# WaterMonitorV2_1.net
KiCad netlist of a schematic drawn in EAGLE
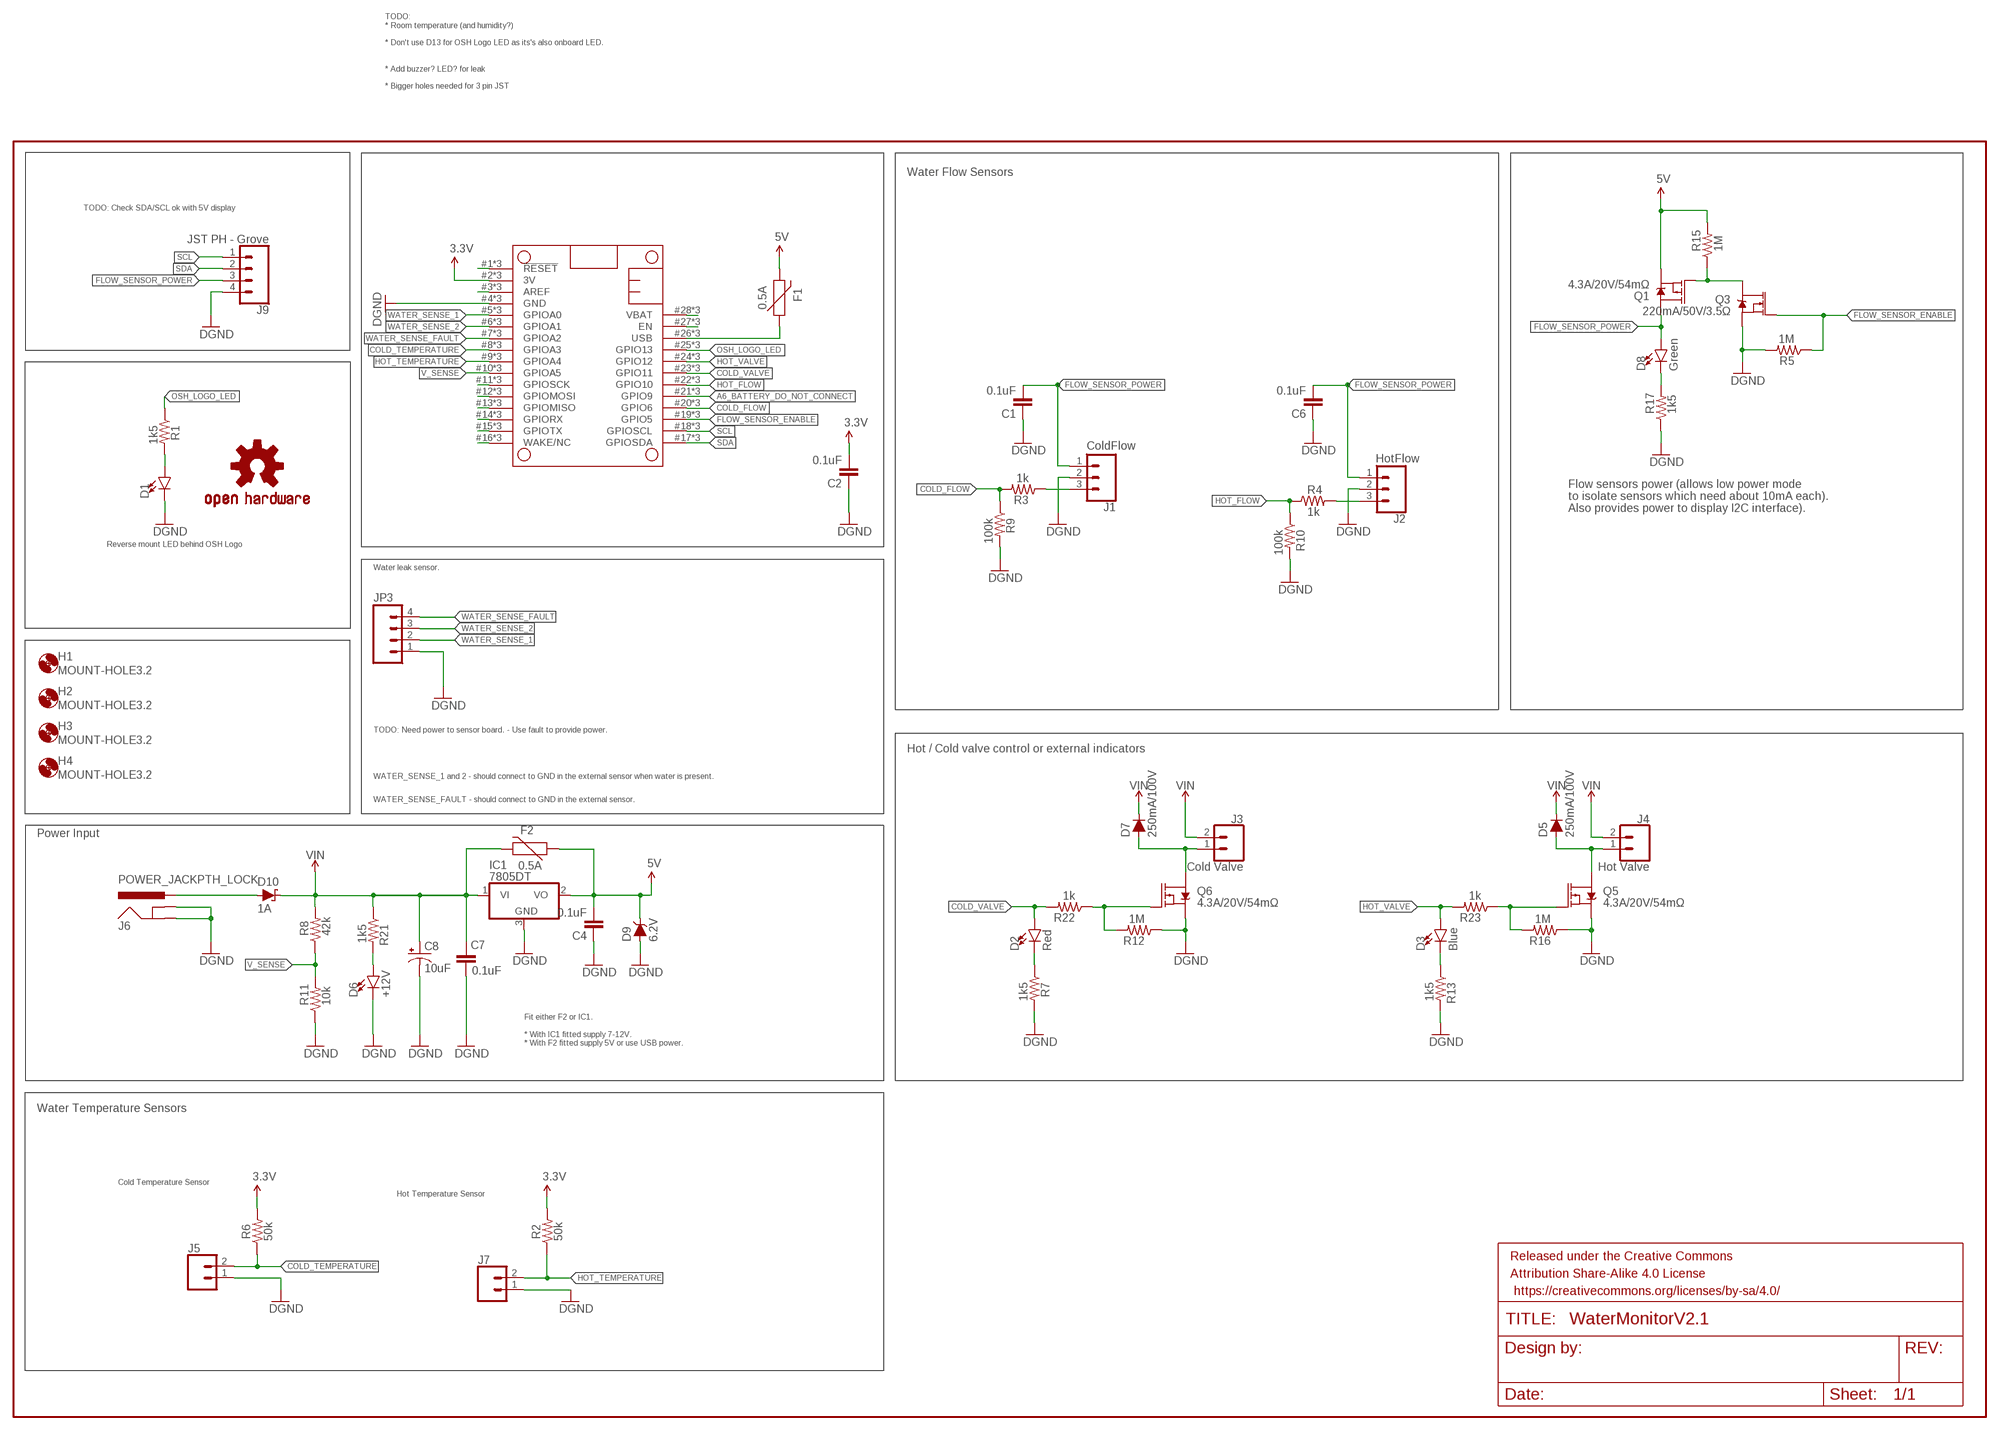
[diagram p0: schematic, sheet 1]

(export (version "E")
  (design (tool "Eeschema 10.0.6"))
  (components
    (comp (ref "C1")
      (value "0.1uF")
      (footprint "eagle-import:0805")
      (libsource (lib "eagle-import") (part "CAP0805"))
    )
    (comp (ref "C2")
      (value "0.1uF")
      (footprint "eagle-import:0805")
      (libsource (lib "eagle-import") (part "CAP0805"))
    )
    (comp (ref "C4")
      (value "0.1uF")
      (footprint "eagle-import:0805")
      (libsource (lib "eagle-import") (part "CAP0805"))
    )
    (comp (ref "C6")
      (value "0.1uF")
      (footprint "eagle-import:0805")
      (libsource (lib "eagle-import") (part "CAP0805"))
    )
    (comp (ref "C7")
      (value "0.1uF")
      (footprint "eagle-import:0805")
      (libsource (lib "eagle-import") (part "CAP0805"))
    )
    (comp (ref "C8")
      (value "10uF")
      (footprint "eagle-import:EIA3216")
      (libsource (lib "eagle-import") (part "10UF-POLAR-EIA3216-16V-10%(TANT)"))
    )
    (comp (ref "D1")
      (value "LED1206-BOTTOM")
      (footprint "eagle-import:LED-1206-BOTTOM")
      (libsource (lib "eagle-import") (part "LED1206-BOTTOM"))
    )
    (comp (ref "D2")
      (value "Red")
      (footprint "eagle-import:LED-1206")
      (libsource (lib "eagle-import") (part "LED-BLUE1206"))
    )
    (comp (ref "D3")
      (value "Blue")
      (footprint "eagle-import:LED-1206")
      (libsource (lib "eagle-import") (part "LED-BLUE1206"))
    )
    (comp (ref "D5")
      (value "250mA/100V")
      (footprint "eagle-import:SOD-323")
      (libsource (lib "eagle-import") (part "DIODE-BAS16J"))
    )
    (comp (ref "D6")
      (value "+12V")
      (footprint "eagle-import:LED-1206")
      (libsource (lib "eagle-import") (part "LED-BLUE1206"))
    )
    (comp (ref "D7")
      (value "250mA/100V")
      (footprint "eagle-import:SOD-323")
      (libsource (lib "eagle-import") (part "DIODE-BAS16J"))
    )
    (comp (ref "D8")
      (value "Green")
      (footprint "eagle-import:LED-1206")
      (libsource (lib "eagle-import") (part "LED-BLUE1206"))
    )
    (comp (ref "D9")
      (value "6.2V")
      (footprint "eagle-import:SOD-323")
      (fields (field (name "MFG") "BZT52C6V2"))
      (libsource (lib "eagle-import") (part "DIODE-ZENER-BZT52C3V6S"))
    )
    (comp (ref "D10")
      (value "1A")
      (footprint "eagle-import:SMA-DIODE")
      (libsource (lib "eagle-import") (part "DIODE-SCHOTTKY-B340A"))
    )
    (comp (ref "F1")
      (value "0.5A")
      (footprint "eagle-import:1206")
      (libsource (lib "eagle-import") (part "PPTC_HALF-AMP"))
    )
    (comp (ref "F2")
      (value "0.5A")
      (footprint "eagle-import:1206")
      (libsource (lib "eagle-import") (part "PPTC_HALF-AMP"))
    )
    (comp (ref "FRAME2")
      (value "FRAME-LEDGER")
      (footprint "eagle-import:CREATIVE_COMMONS")
      (libsource (lib "eagle-import") (part "FRAME-LEDGER"))
    )
    (comp (ref "H1")
      (value "MOUNT-HOLE3.2")
      (footprint "eagle-import:3,2")
      (libsource (lib "eagle-import") (part "MOUNT-HOLE3.2"))
    )
    (comp (ref "H2")
      (value "MOUNT-HOLE3.2")
      (footprint "eagle-import:3,2")
      (libsource (lib "eagle-import") (part "MOUNT-HOLE3.2"))
    )
    (comp (ref "H3")
      (value "MOUNT-HOLE3.2")
      (footprint "eagle-import:3,2")
      (libsource (lib "eagle-import") (part "MOUNT-HOLE3.2"))
    )
    (comp (ref "H4")
      (value "MOUNT-HOLE3.2")
      (footprint "eagle-import:3,2")
      (libsource (lib "eagle-import") (part "MOUNT-HOLE3.2"))
    )
    (comp (ref "IC1")
      (value "7805DT")
      (footprint "eagle-import:TO252")
      (libsource (lib "eagle-import") (part "78DT05"))
    )
    (comp (ref "J1")
      (value "ColdFlow")
      (footprint "eagle-import:JST-HX-3-PTH-VERT")
      (libsource (lib "eagle-import") (part "CONN_03JST-HX-PTH-VERT"))
    )
    (comp (ref "J2")
      (value "HotFlow")
      (footprint "eagle-import:JST-HX-3-PTH-VERT")
      (libsource (lib "eagle-import") (part "CONN_03JST-HX-PTH-VERT"))
    )
    (comp (ref "J3")
      (value "Cold Valve")
      (footprint "eagle-import:SCREWTERMINAL-5MM-2")
      (libsource (lib "eagle-import") (part "CONN_025MM"))
    )
    (comp (ref "J4")
      (value "Hot Valve")
      (footprint "eagle-import:SCREWTERMINAL-5MM-2")
      (libsource (lib "eagle-import") (part "CONN_025MM"))
    )
    (comp (ref "J5")
      (value "CONN_02POLAR")
      (footprint "eagle-import:MOLEX-1X2")
      (libsource (lib "eagle-import") (part "CONN_02POLAR"))
    )
    (comp (ref "J6")
      (value "POWER_JACKPTH_LOCK")
      (footprint "eagle-import:POWER_JACK_PTH_LOCK")
      (libsource (lib "eagle-import") (part "POWER_JACKPTH_LOCK"))
    )
    (comp (ref "J7")
      (value "CONN_02POLAR")
      (footprint "eagle-import:MOLEX-1X2")
      (libsource (lib "eagle-import") (part "CONN_02POLAR"))
    )
    (comp (ref "J9")
      (value "JST PH - Grove")
      (footprint "eagle-import:JST-4-PTH-VERT")
      (libsource (lib "eagle-import") (part "CONN_04JST-PTH-VERT"))
    )
    (comp (ref "JP3")
      (value "M04POLAR")
      (footprint "eagle-import:MOLEX-1X4@1")
      (libsource (lib "eagle-import") (part "M04POLAR"))
    )
    (comp (ref "LOGO1")
      (value "OSHW-LOGOM")
      (footprint "eagle-import:OSHW-LOGO-M")
      (libsource (lib "eagle-import") (part "OSHW-LOGOM"))
    )
    (comp (ref "MS1")
      (value "FEATHERWINGFEATHEWING_BREAKOUT")
      (footprint "eagle-import:FEATHERWING_BREAKOUT")
      (libsource (lib "eagle-import") (part "FEATHERWINGFEATHEWING_BREAKOUT"))
    )
    (comp (ref "Q1")
      (value "4.3A/20V/54mΩ")
      (footprint "eagle-import:SOT23-3")
      (libsource (lib "eagle-import") (part "MOSFET_PCH-IRLML2244"))
    )
    (comp (ref "Q3")
      (value "220mA/50V/3.5Ω")
      (footprint "eagle-import:SOT23-3")
      (libsource (lib "eagle-import") (part "MOSFET-NCH-BSS138"))
    )
    (comp (ref "Q5")
      (value "4.3A/20V/54mΩ")
      (footprint "eagle-import:SOT23-3")
      (libsource (lib "eagle-import") (part "MOSFET_PCH-IRLML2244"))
    )
    (comp (ref "Q6")
      (value "4.3A/20V/54mΩ")
      (footprint "eagle-import:SOT23-3")
      (libsource (lib "eagle-import") (part "MOSFET_PCH-IRLML2244"))
    )
    (comp (ref "R1")
      (value "1k5")
      (footprint "eagle-import:0805")
      (libsource (lib "eagle-import") (part "RESISTOR0805"))
    )
    (comp (ref "R2")
      (value "50k")
      (footprint "eagle-import:0805")
      (libsource (lib "eagle-import") (part "RESISTOR0805"))
    )
    (comp (ref "R3")
      (value "1k")
      (footprint "eagle-import:0805")
      (libsource (lib "eagle-import") (part "RESISTOR0805"))
    )
    (comp (ref "R4")
      (value "1k")
      (footprint "eagle-import:0805")
      (libsource (lib "eagle-import") (part "RESISTOR0805"))
    )
    (comp (ref "R5")
      (value "1M")
      (footprint "eagle-import:0805")
      (libsource (lib "eagle-import") (part "RESISTOR0805"))
    )
    (comp (ref "R6")
      (value "50k")
      (footprint "eagle-import:0805")
      (libsource (lib "eagle-import") (part "RESISTOR0805"))
    )
    (comp (ref "R7")
      (value "1k5")
      (footprint "eagle-import:0805")
      (libsource (lib "eagle-import") (part "RESISTOR0805"))
    )
    (comp (ref "R8")
      (value "42k")
      (footprint "eagle-import:0805")
      (libsource (lib "eagle-import") (part "RESISTOR0805"))
    )
    (comp (ref "R9")
      (value "100k")
      (footprint "eagle-import:0805")
      (libsource (lib "eagle-import") (part "RESISTOR0805"))
    )
    (comp (ref "R10")
      (value "100k")
      (footprint "eagle-import:0805")
      (libsource (lib "eagle-import") (part "RESISTOR0805"))
    )
    (comp (ref "R11")
      (value "10k")
      (footprint "eagle-import:0805")
      (libsource (lib "eagle-import") (part "RESISTOR0805"))
    )
    (comp (ref "R12")
      (value "1M")
      (footprint "eagle-import:0805")
      (libsource (lib "eagle-import") (part "RESISTOR0805"))
    )
    (comp (ref "R13")
      (value "1k5")
      (footprint "eagle-import:0805")
      (libsource (lib "eagle-import") (part "RESISTOR0805"))
    )
    (comp (ref "R15")
      (value "1M")
      (footprint "eagle-import:0805")
      (libsource (lib "eagle-import") (part "RESISTOR0805"))
    )
    (comp (ref "R16")
      (value "1M")
      (footprint "eagle-import:0805")
      (libsource (lib "eagle-import") (part "RESISTOR0805"))
    )
    (comp (ref "R17")
      (value "1k5")
      (footprint "eagle-import:0805")
      (libsource (lib "eagle-import") (part "RESISTOR0805"))
    )
    (comp (ref "R21")
      (value "1k5")
      (footprint "eagle-import:0805")
      (libsource (lib "eagle-import") (part "RESISTOR0805"))
    )
    (comp (ref "R22")
      (value "1k")
      (footprint "eagle-import:0805")
      (libsource (lib "eagle-import") (part "RESISTOR0805"))
    )
    (comp (ref "R23")
      (value "1k")
      (footprint "eagle-import:0805")
      (libsource (lib "eagle-import") (part "RESISTOR0805"))
    )
  )
  (nets
    (net (code "1") (name "3.3V") (class "Default")
      (node (ref "C2") (pin "2") (pinfunction "2_2") (pintype "passive"))
      (node (ref "MS1") (pin "#2") (pinfunction "3V_#2") (pintype "power_in"))
      (node (ref "MS1") (pin "2") (pinfunction "3V_2") (pintype "power_in"))
      (node (ref "MS1") (pin "@2") (pinfunction "3V_@2") (pintype "power_in"))
      (node (ref "R2") (pin "2") (pinfunction "2_2") (pintype "passive"))
      (node (ref "R6") (pin "2") (pinfunction "2_2") (pintype "passive"))
    )
    (net (code "2") (name "5V") (class "Default")
      (node (ref "C4") (pin "2") (pinfunction "2_2") (pintype "passive"))
      (node (ref "D9") (pin "C") (pinfunction "C_C") (pintype "passive"))
      (node (ref "F1") (pin "2") (pinfunction "2_2") (pintype "bidirectional"))
      (node (ref "F2") (pin "1") (pinfunction "1_1") (pintype "bidirectional"))
      (node (ref "IC1") (pin "2") (pinfunction "VO_2") (pintype "passive"))
      (node (ref "Q1") (pin "2") (pinfunction "S_2") (pintype "bidirectional"))
      (node (ref "R15") (pin "2") (pinfunction "2_2") (pintype "passive"))
    )
    (net (code "3") (name "A6_BATTERY_DO_NOT_CONNECT") (class "Default")
      (node (ref "MS1") (pin "#21") (pinfunction "GPIO9_#21") (pintype "bidirectional"))
      (node (ref "MS1") (pin "21") (pinfunction "GPIO9_21") (pintype "bidirectional"))
      (node (ref "MS1") (pin "@21") (pinfunction "GPIO9_@21") (pintype "bidirectional"))
    )
    (net (code "4") (name "COLD_FLOW") (class "Default")
      (node (ref "MS1") (pin "#20") (pinfunction "GPIO6_#20") (pintype "bidirectional"))
      (node (ref "MS1") (pin "20") (pinfunction "GPIO6_20") (pintype "bidirectional"))
      (node (ref "MS1") (pin "@20") (pinfunction "GPIO6_@20") (pintype "bidirectional"))
      (node (ref "R3") (pin "2") (pinfunction "2_2") (pintype "passive"))
      (node (ref "R9") (pin "1") (pinfunction "1_1") (pintype "passive"))
    )
    (net (code "5") (name "COLD_TEMPERATURE") (class "Default")
      (node (ref "J5") (pin "2") (pinfunction "2_2") (pintype "passive"))
      (node (ref "MS1") (pin "#8") (pinfunction "GPIOA3_#8") (pintype "bidirectional"))
      (node (ref "MS1") (pin "8") (pinfunction "GPIOA3_8") (pintype "bidirectional"))
      (node (ref "MS1") (pin "@8") (pinfunction "GPIOA3_@8") (pintype "bidirectional"))
      (node (ref "R6") (pin "1") (pinfunction "1_1") (pintype "passive"))
    )
    (net (code "6") (name "COLD_VALVE") (class "Default")
      (node (ref "D2") (pin "A") (pinfunction "A_A") (pintype "passive"))
      (node (ref "MS1") (pin "#23") (pinfunction "GPIO11_#23") (pintype "bidirectional"))
      (node (ref "MS1") (pin "23") (pinfunction "GPIO11_23") (pintype "bidirectional"))
      (node (ref "MS1") (pin "@23") (pinfunction "GPIO11_@23") (pintype "bidirectional"))
      (node (ref "R22") (pin "2") (pinfunction "2_2") (pintype "passive"))
    )
    (net (code "7") (name "DGND") (class "Default")
      (node (ref "C1") (pin "1") (pinfunction "1_1") (pintype "passive"))
      (node (ref "C2") (pin "1") (pinfunction "1_1") (pintype "passive"))
      (node (ref "C4") (pin "1") (pinfunction "1_1") (pintype "passive"))
      (node (ref "C6") (pin "1") (pinfunction "1_1") (pintype "passive"))
      (node (ref "C7") (pin "1") (pinfunction "1_1") (pintype "passive"))
      (node (ref "C8") (pin "-") (pinfunction "-_-") (pintype "passive"))
      (node (ref "D1") (pin "C") (pinfunction "C_C") (pintype "passive"))
      (node (ref "D6") (pin "C") (pinfunction "C_C") (pintype "passive"))
      (node (ref "D9") (pin "A") (pinfunction "A_A") (pintype "passive"))
      (node (ref "IC1") (pin "3") (pinfunction "GND_3") (pintype "passive"))
      (node (ref "J1") (pin "2") (pinfunction "2_2") (pintype "passive"))
      (node (ref "J2") (pin "2") (pinfunction "2_2") (pintype "passive"))
      (node (ref "J5") (pin "1") (pinfunction "1_1") (pintype "passive"))
      (node (ref "J6") (pin "GND") (pinfunction "GND_GND") (pintype "bidirectional"))
      (node (ref "J6") (pin "GNDBREAK") (pinfunction "GNDBREAK_GNDBREAK") (pintype "bidirectional"))
      (node (ref "J7") (pin "1") (pinfunction "1_1") (pintype "passive"))
      (node (ref "J9") (pin "4") (pinfunction "4_4") (pintype "passive"))
      (node (ref "JP3") (pin "1") (pinfunction "1_1") (pintype "passive"))
      (node (ref "MS1") (pin "#4") (pinfunction "GND_#4") (pintype "power_in"))
      (node (ref "MS1") (pin "4") (pinfunction "GND_4") (pintype "power_in"))
      (node (ref "MS1") (pin "@4") (pinfunction "GND_@4") (pintype "power_in"))
      (node (ref "Q3") (pin "2") (pinfunction "S_2") (pintype "bidirectional"))
      (node (ref "Q5") (pin "2") (pinfunction "S_2") (pintype "bidirectional"))
      (node (ref "Q6") (pin "2") (pinfunction "S_2") (pintype "bidirectional"))
      (node (ref "R10") (pin "2") (pinfunction "2_2") (pintype "passive"))
      (node (ref "R11") (pin "1") (pinfunction "1_1") (pintype "passive"))
      (node (ref "R12") (pin "1") (pinfunction "1_1") (pintype "passive"))
      (node (ref "R13") (pin "2") (pinfunction "2_2") (pintype "passive"))
      (node (ref "R16") (pin "1") (pinfunction "1_1") (pintype "passive"))
      (node (ref "R17") (pin "1") (pinfunction "1_1") (pintype "passive"))
      (node (ref "R5") (pin "2") (pinfunction "2_2") (pintype "passive"))
      (node (ref "R7") (pin "2") (pinfunction "2_2") (pintype "passive"))
      (node (ref "R9") (pin "2") (pinfunction "2_2") (pintype "passive"))
    )
    (net (code "8") (name "FLOW_SENSOR_ENABLE") (class "Default")
      (node (ref "MS1") (pin "#19") (pinfunction "GPIO5_#19") (pintype "bidirectional"))
      (node (ref "MS1") (pin "19") (pinfunction "GPIO5_19") (pintype "bidirectional"))
      (node (ref "MS1") (pin "@19") (pinfunction "GPIO5_@19") (pintype "bidirectional"))
      (node (ref "Q3") (pin "1") (pinfunction "G_1") (pintype "bidirectional"))
      (node (ref "R5") (pin "1") (pinfunction "1_1") (pintype "passive"))
    )
    (net (code "9") (name "FLOW_SENSOR_POWER") (class "Default")
      (node (ref "C1") (pin "2") (pinfunction "2_2") (pintype "passive"))
      (node (ref "C6") (pin "2") (pinfunction "2_2") (pintype "passive"))
      (node (ref "D8") (pin "A") (pinfunction "A_A") (pintype "passive"))
      (node (ref "J1") (pin "1") (pinfunction "1_1") (pintype "passive"))
      (node (ref "J2") (pin "1") (pinfunction "1_1") (pintype "passive"))
      (node (ref "J9") (pin "3") (pinfunction "3_3") (pintype "passive"))
      (node (ref "Q1") (pin "3") (pinfunction "D_3") (pintype "bidirectional"))
    )
    (net (code "10") (name "HOT_FLOW") (class "Default")
      (node (ref "MS1") (pin "#22") (pinfunction "GPIO10_#22") (pintype "bidirectional"))
      (node (ref "MS1") (pin "22") (pinfunction "GPIO10_22") (pintype "bidirectional"))
      (node (ref "MS1") (pin "@22") (pinfunction "GPIO10_@22") (pintype "bidirectional"))
      (node (ref "R10") (pin "1") (pinfunction "1_1") (pintype "passive"))
      (node (ref "R4") (pin "1") (pinfunction "1_1") (pintype "passive"))
    )
    (net (code "11") (name "HOT_TEMPERATURE") (class "Default")
      (node (ref "J7") (pin "2") (pinfunction "2_2") (pintype "passive"))
      (node (ref "MS1") (pin "#9") (pinfunction "GPIOA4_#9") (pintype "bidirectional"))
      (node (ref "MS1") (pin "9") (pinfunction "GPIOA4_9") (pintype "bidirectional"))
      (node (ref "MS1") (pin "@9") (pinfunction "GPIOA4_@9") (pintype "bidirectional"))
      (node (ref "R2") (pin "1") (pinfunction "1_1") (pintype "passive"))
    )
    (net (code "12") (name "HOT_VALVE") (class "Default")
      (node (ref "D3") (pin "A") (pinfunction "A_A") (pintype "passive"))
      (node (ref "MS1") (pin "#24") (pinfunction "GPIO12_#24") (pintype "bidirectional"))
      (node (ref "MS1") (pin "24") (pinfunction "GPIO12_24") (pintype "bidirectional"))
      (node (ref "MS1") (pin "@24") (pinfunction "GPIO12_@24") (pintype "bidirectional"))
      (node (ref "R23") (pin "2") (pinfunction "2_2") (pintype "passive"))
    )
    (net (code "13") (name "Net-(D1-PadA)") (class "Default")
      (node (ref "D1") (pin "A") (pinfunction "A_A") (pintype "passive"))
      (node (ref "R1") (pin "2") (pinfunction "2_2") (pintype "passive"))
    )
    (net (code "14") (name "Net-(D2-PadC)") (class "Default")
      (node (ref "D2") (pin "C") (pinfunction "C_C") (pintype "passive"))
      (node (ref "R7") (pin "1") (pinfunction "1_1") (pintype "passive"))
    )
    (net (code "15") (name "Net-(D3-PadC)") (class "Default")
      (node (ref "D3") (pin "C") (pinfunction "C_C") (pintype "passive"))
      (node (ref "R13") (pin "1") (pinfunction "1_1") (pintype "passive"))
    )
    (net (code "16") (name "Net-(D6-PadA)") (class "Default")
      (node (ref "D6") (pin "A") (pinfunction "A_A") (pintype "passive"))
      (node (ref "R21") (pin "2") (pinfunction "2_2") (pintype "passive"))
    )
    (net (code "17") (name "Net-(D8-PadC)") (class "Default")
      (node (ref "D8") (pin "C") (pinfunction "C_C") (pintype "passive"))
      (node (ref "R17") (pin "2") (pinfunction "2_2") (pintype "passive"))
    )
    (net (code "18") (name "Net-(D10-PadA)") (class "Default")
      (node (ref "D10") (pin "A") (pinfunction "A_A") (pintype "passive"))
      (node (ref "J6") (pin "PWR") (pinfunction "PWR_PWR") (pintype "bidirectional"))
    )
    (net (code "19") (name "Net-(F1-Pad1)") (class "Default")
      (node (ref "F1") (pin "1") (pinfunction "1_1") (pintype "bidirectional"))
      (node (ref "MS1") (pin "#26") (pinfunction "USB_#26") (pintype "power_in"))
      (node (ref "MS1") (pin "26") (pinfunction "USB_26") (pintype "power_in"))
      (node (ref "MS1") (pin "@26") (pinfunction "USB_@26") (pintype "power_in"))
    )
    (net (code "20") (name "Net-(J1-Pad3)") (class "Default")
      (node (ref "J1") (pin "3") (pinfunction "3_3") (pintype "passive"))
      (node (ref "R3") (pin "1") (pinfunction "1_1") (pintype "passive"))
    )
    (net (code "21") (name "Net-(J2-Pad3)") (class "Default")
      (node (ref "J2") (pin "3") (pinfunction "3_3") (pintype "passive"))
      (node (ref "R4") (pin "2") (pinfunction "2_2") (pintype "passive"))
    )
    (net (code "22") (name "Net-(MS1-AREF-Pad#3)") (class "Default")
      (node (ref "MS1") (pin "#3") (pinfunction "AREF_#3") (pintype "passive"))
      (node (ref "MS1") (pin "3") (pinfunction "AREF_3") (pintype "passive"))
      (node (ref "MS1") (pin "@3") (pinfunction "AREF_@3") (pintype "passive"))
    )
    (net (code "23") (name "Net-(MS1-EN-Pad#27)") (class "Default")
      (node (ref "MS1") (pin "#27") (pinfunction "EN_#27") (pintype "passive"))
      (node (ref "MS1") (pin "27") (pinfunction "EN_27") (pintype "passive"))
      (node (ref "MS1") (pin "@27") (pinfunction "EN_@27") (pintype "passive"))
    )
    (net (code "24") (name "Net-(MS1-GPIOMISO-Pad#13)") (class "Default")
      (node (ref "MS1") (pin "#13") (pinfunction "GPIOMISO_#13") (pintype "bidirectional"))
      (node (ref "MS1") (pin "13") (pinfunction "GPIOMISO_13") (pintype "bidirectional"))
      (node (ref "MS1") (pin "@13") (pinfunction "GPIOMISO_@13") (pintype "bidirectional"))
    )
    (net (code "25") (name "Net-(MS1-GPIOMOSI-Pad#12)") (class "Default")
      (node (ref "MS1") (pin "#12") (pinfunction "GPIOMOSI_#12") (pintype "bidirectional"))
      (node (ref "MS1") (pin "12") (pinfunction "GPIOMOSI_12") (pintype "bidirectional"))
      (node (ref "MS1") (pin "@12") (pinfunction "GPIOMOSI_@12") (pintype "bidirectional"))
    )
    (net (code "26") (name "Net-(MS1-GPIORX-Pad#14)") (class "Default")
      (node (ref "MS1") (pin "#14") (pinfunction "GPIORX_#14") (pintype "bidirectional"))
      (node (ref "MS1") (pin "14") (pinfunction "GPIORX_14") (pintype "bidirectional"))
      (node (ref "MS1") (pin "@14") (pinfunction "GPIORX_@14") (pintype "bidirectional"))
    )
    (net (code "27") (name "Net-(MS1-GPIOSCK-Pad#11)") (class "Default")
      (node (ref "MS1") (pin "#11") (pinfunction "GPIOSCK_#11") (pintype "bidirectional"))
      (node (ref "MS1") (pin "11") (pinfunction "GPIOSCK_11") (pintype "bidirectional"))
      (node (ref "MS1") (pin "@11") (pinfunction "GPIOSCK_@11") (pintype "bidirectional"))
    )
    (net (code "28") (name "Net-(MS1-GPIOTX-Pad#15)") (class "Default")
      (node (ref "MS1") (pin "#15") (pinfunction "GPIOTX_#15") (pintype "bidirectional"))
      (node (ref "MS1") (pin "15") (pinfunction "GPIOTX_15") (pintype "bidirectional"))
      (node (ref "MS1") (pin "@15") (pinfunction "GPIOTX_@15") (pintype "bidirectional"))
    )
    (net (code "29") (name "Net-(MS1-VBAT-Pad#28)") (class "Default")
      (node (ref "MS1") (pin "#28") (pinfunction "VBAT_#28") (pintype "power_in"))
      (node (ref "MS1") (pin "28") (pinfunction "VBAT_28") (pintype "power_in"))
      (node (ref "MS1") (pin "@28") (pinfunction "VBAT_@28") (pintype "power_in"))
    )
    (net (code "30") (name "Net-(MS1-WAKE{slash}NC-Pad#16)") (class "Default")
      (node (ref "MS1") (pin "#16") (pinfunction "WAKE/NC_#16") (pintype "passive"))
      (node (ref "MS1") (pin "16") (pinfunction "WAKE/NC_16") (pintype "passive"))
      (node (ref "MS1") (pin "@16") (pinfunction "WAKE/NC_@16") (pintype "passive"))
    )
    (net (code "31") (name "Net-(MS1-~{RESET}-Pad#1)") (class "Default")
      (node (ref "MS1") (pin "#1") (pinfunction "~{RESET}_#1") (pintype "input"))
      (node (ref "MS1") (pin "1") (pinfunction "~{RESET}_1") (pintype "input"))
      (node (ref "MS1") (pin "@1") (pinfunction "~{RESET}_@1") (pintype "input"))
    )
    (net (code "32") (name "Net-(Q1-G)") (class "Default")
      (node (ref "Q1") (pin "1") (pinfunction "G_1") (pintype "bidirectional"))
      (node (ref "Q3") (pin "3") (pinfunction "D_3") (pintype "bidirectional"))
      (node (ref "R15") (pin "1") (pinfunction "1_1") (pintype "passive"))
    )
    (net (code "33") (name "Net-(Q5-D)") (class "Default")
      (node (ref "D5") (pin "A") (pinfunction "A_A") (pintype "passive"))
      (node (ref "J4") (pin "1") (pinfunction "1_1") (pintype "passive"))
      (node (ref "Q5") (pin "3") (pinfunction "D_3") (pintype "bidirectional"))
    )
    (net (code "34") (name "Net-(Q5-G)") (class "Default")
      (node (ref "Q5") (pin "1") (pinfunction "G_1") (pintype "bidirectional"))
      (node (ref "R16") (pin "2") (pinfunction "2_2") (pintype "passive"))
      (node (ref "R23") (pin "1") (pinfunction "1_1") (pintype "passive"))
    )
    (net (code "35") (name "Net-(Q6-D)") (class "Default")
      (node (ref "D7") (pin "A") (pinfunction "A_A") (pintype "passive"))
      (node (ref "J3") (pin "1") (pinfunction "1_1") (pintype "passive"))
      (node (ref "Q6") (pin "3") (pinfunction "D_3") (pintype "bidirectional"))
    )
    (net (code "36") (name "Net-(Q6-G)") (class "Default")
      (node (ref "Q6") (pin "1") (pinfunction "G_1") (pintype "bidirectional"))
      (node (ref "R12") (pin "2") (pinfunction "2_2") (pintype "passive"))
      (node (ref "R22") (pin "1") (pinfunction "1_1") (pintype "passive"))
    )
    (net (code "37") (name "OSH_LOGO_LED") (class "Default")
      (node (ref "MS1") (pin "#25") (pinfunction "GPIO13_#25") (pintype "bidirectional"))
      (node (ref "MS1") (pin "25") (pinfunction "GPIO13_25") (pintype "bidirectional"))
      (node (ref "MS1") (pin "@25") (pinfunction "GPIO13_@25") (pintype "bidirectional"))
      (node (ref "R1") (pin "1") (pinfunction "1_1") (pintype "passive"))
    )
    (net (code "38") (name "SCL") (class "Default")
      (node (ref "J9") (pin "1") (pinfunction "1_1") (pintype "passive"))
      (node (ref "MS1") (pin "#18") (pinfunction "GPIOSCL_#18") (pintype "bidirectional"))
      (node (ref "MS1") (pin "18") (pinfunction "GPIOSCL_18") (pintype "bidirectional"))
      (node (ref "MS1") (pin "@!8") (pinfunction "GPIOSCL_@!8") (pintype "bidirectional"))
    )
    (net (code "39") (name "SDA") (class "Default")
      (node (ref "J9") (pin "2") (pinfunction "2_2") (pintype "passive"))
      (node (ref "MS1") (pin "#17") (pinfunction "GPIOSDA_#17") (pintype "bidirectional"))
      (node (ref "MS1") (pin "17") (pinfunction "GPIOSDA_17") (pintype "bidirectional"))
      (node (ref "MS1") (pin "@17") (pinfunction "GPIOSDA_@17") (pintype "bidirectional"))
    )
    (net (code "40") (name "VIN") (class "Default")
      (node (ref "C7") (pin "2") (pinfunction "2_2") (pintype "passive"))
      (node (ref "C8") (pin "+") (pinfunction "+_+") (pintype "passive"))
      (node (ref "D10") (pin "C") (pinfunction "C_C") (pintype "passive"))
      (node (ref "D5") (pin "C") (pinfunction "C_C") (pintype "passive"))
      (node (ref "D7") (pin "C") (pinfunction "C_C") (pintype "passive"))
      (node (ref "F2") (pin "2") (pinfunction "2_2") (pintype "bidirectional"))
      (node (ref "IC1") (pin "1") (pinfunction "VI_1") (pintype "input"))
      (node (ref "J3") (pin "2") (pinfunction "2_2") (pintype "passive"))
      (node (ref "J4") (pin "2") (pinfunction "2_2") (pintype "passive"))
      (node (ref "R21") (pin "1") (pinfunction "1_1") (pintype "passive"))
      (node (ref "R8") (pin "2") (pinfunction "2_2") (pintype "passive"))
    )
    (net (code "41") (name "V_SENSE") (class "Default")
      (node (ref "MS1") (pin "#10") (pinfunction "GPIOA5_#10") (pintype "bidirectional"))
      (node (ref "MS1") (pin "10") (pinfunction "GPIOA5_10") (pintype "bidirectional"))
      (node (ref "MS1") (pin "@10") (pinfunction "GPIOA5_@10") (pintype "bidirectional"))
      (node (ref "R11") (pin "2") (pinfunction "2_2") (pintype "passive"))
      (node (ref "R8") (pin "1") (pinfunction "1_1") (pintype "passive"))
    )
    (net (code "42") (name "WATER_SENSE_1") (class "Default")
      (node (ref "JP3") (pin "2") (pinfunction "2_2") (pintype "passive"))
      (node (ref "MS1") (pin "#5") (pinfunction "GPIOA0_#5") (pintype "bidirectional"))
      (node (ref "MS1") (pin "5") (pinfunction "GPIOA0_5") (pintype "bidirectional"))
      (node (ref "MS1") (pin "@5") (pinfunction "GPIOA0_@5") (pintype "bidirectional"))
    )
    (net (code "43") (name "WATER_SENSE_2") (class "Default")
      (node (ref "JP3") (pin "3") (pinfunction "3_3") (pintype "passive"))
      (node (ref "MS1") (pin "#6") (pinfunction "GPIOA1_#6") (pintype "bidirectional"))
      (node (ref "MS1") (pin "6") (pinfunction "GPIOA1_6") (pintype "bidirectional"))
      (node (ref "MS1") (pin "@6") (pinfunction "GPIOA1_@6") (pintype "bidirectional"))
    )
    (net (code "44") (name "WATER_SENSE_FAULT") (class "Default")
      (node (ref "JP3") (pin "4") (pinfunction "4_4") (pintype "passive"))
      (node (ref "MS1") (pin "#7") (pinfunction "GPIOA2_#7") (pintype "bidirectional"))
      (node (ref "MS1") (pin "7") (pinfunction "GPIOA2_7") (pintype "bidirectional"))
      (node (ref "MS1") (pin "@7") (pinfunction "GPIOA2_@7") (pintype "bidirectional"))
    )
  )
)
